# usbasp.net
KiCad netlist of a schematic drawn in EAGLE
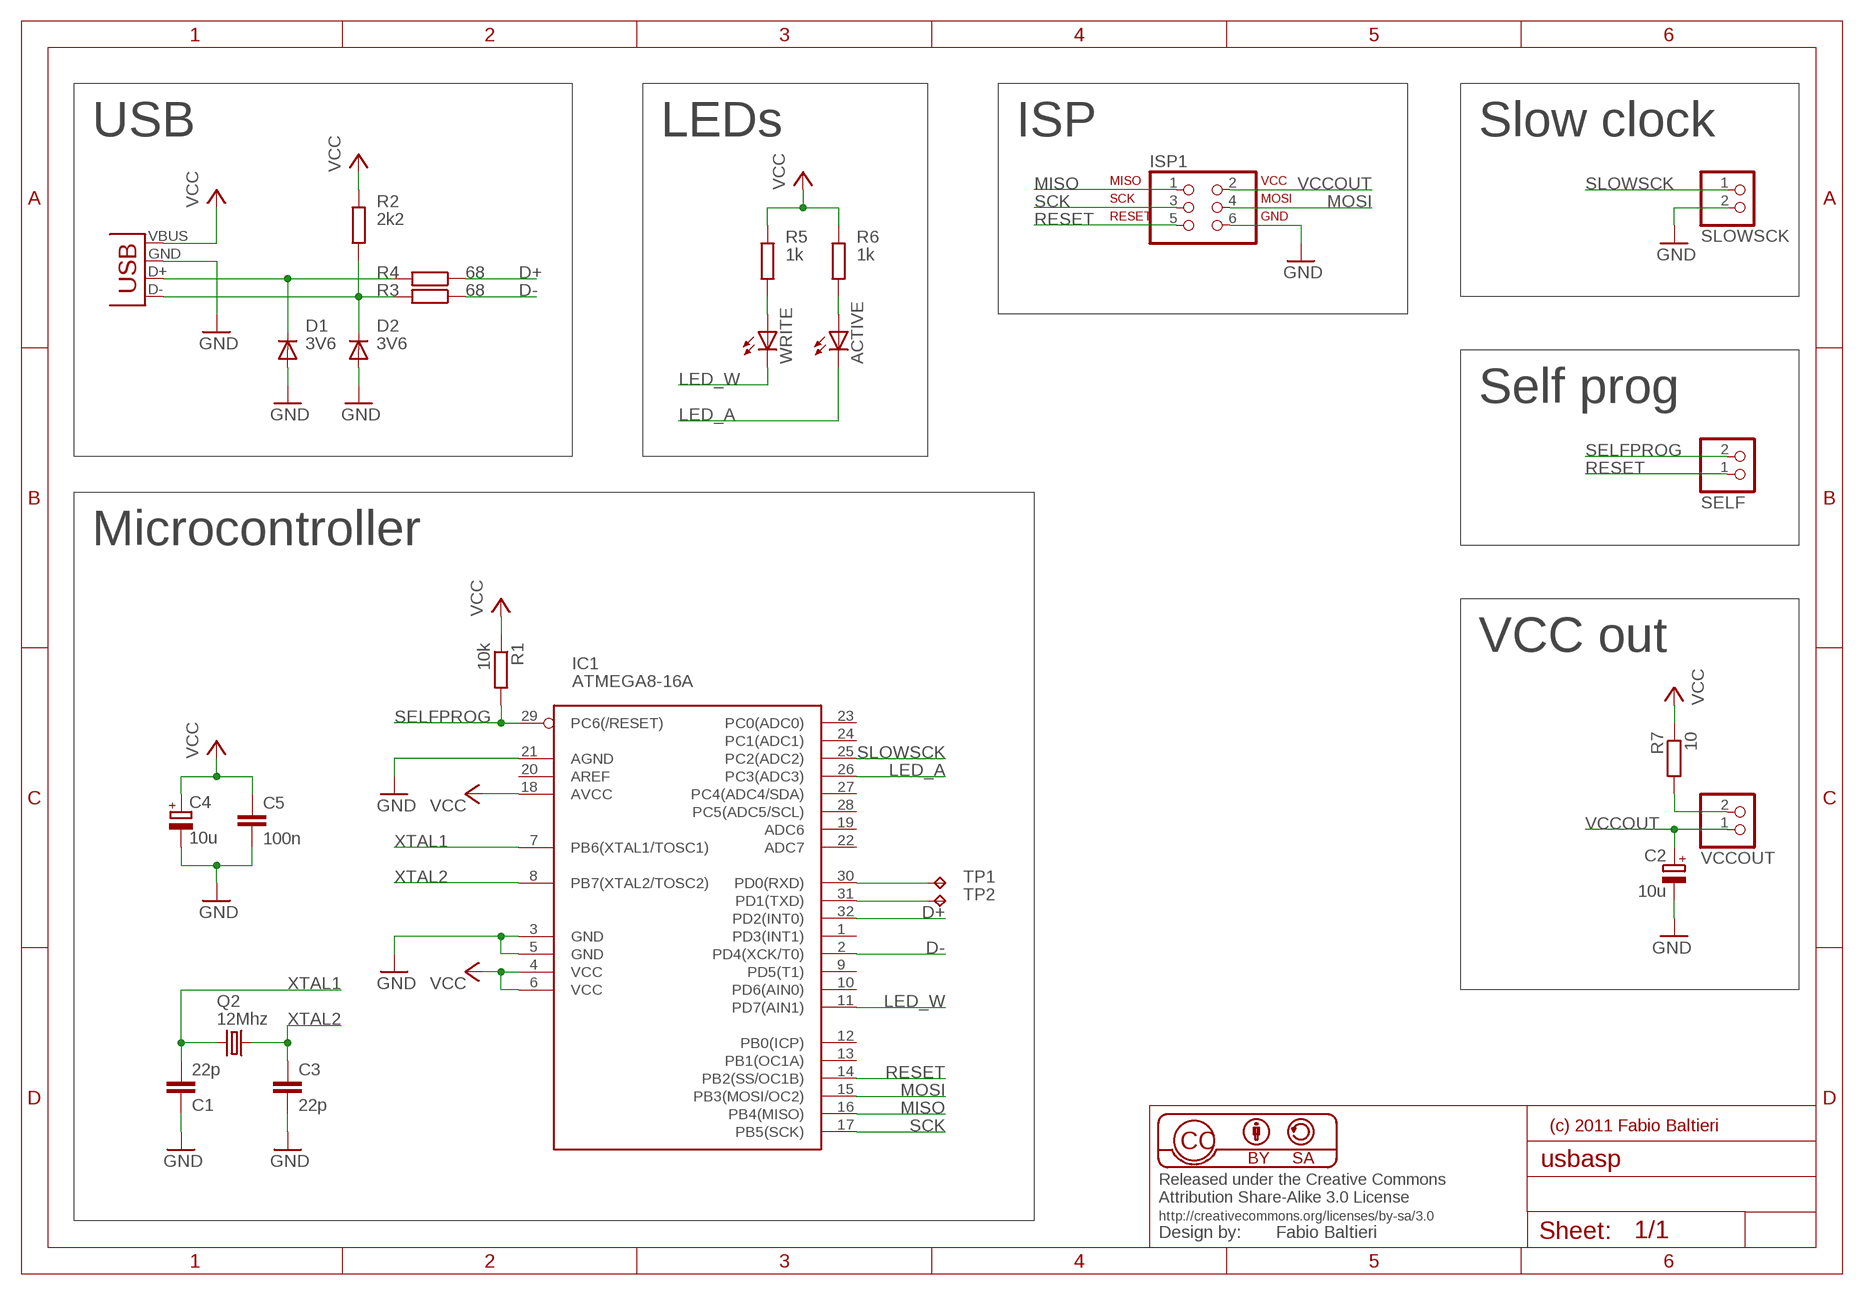
[diagram p0: schematic, sheet 1]

(export (version "E")
  (design (tool "Eeschema 10.0.6"))
  (components
    (comp (ref "ACTIVE")
      (value "LEDCHIP-LED0805")
      (footprint "eagle-import:CHIP-LED0805")
      (libsource (lib "eagle-import") (part "LEDCHIP-LED0805"))
    )
    (comp (ref "C1")
      (value "22p")
      (footprint "eagle-import:C0805")
      (libsource (lib "eagle-import") (part "C-EUC0805"))
    )
    (comp (ref "C2")
      (value "10u")
      (footprint "eagle-import:SMC_A")
      (libsource (lib "eagle-import") (part "CPOL-EUSMCA"))
    )
    (comp (ref "C3")
      (value "22p")
      (footprint "eagle-import:C0805")
      (libsource (lib "eagle-import") (part "C-EUC0805"))
    )
    (comp (ref "C4")
      (value "10u")
      (footprint "eagle-import:SMC_A")
      (libsource (lib "eagle-import") (part "CPOL-EUSMCA"))
    )
    (comp (ref "C5")
      (value "100n")
      (footprint "eagle-import:C0805")
      (libsource (lib "eagle-import") (part "C-EUC0805"))
    )
    (comp (ref "D1")
      (value "3V6")
      (footprint "eagle-import:SMA-DIODE")
      (libsource (lib "eagle-import") (part "DIODESMA"))
    )
    (comp (ref "D2")
      (value "3V6")
      (footprint "eagle-import:SMA-DIODE")
      (libsource (lib "eagle-import") (part "DIODESMA"))
    )
    (comp (ref "IC1")
      (value "ATMEGA8-16A")
      (footprint "eagle-import:TQFP32-08")
      (libsource (lib "eagle-import") (part "ATMEGA8A-16"))
    )
    (comp (ref "ISP1")
      (value "ISP-AVR910SMD")
      (footprint "eagle-import:2X03_BORDER")
      (libsource (lib "eagle-import") (part "ISP-AVR910SMD"))
    )
    (comp (ref "Q2")
      (value "12Mhz")
      (footprint "eagle-import:HC49US")
      (libsource (lib "eagle-import") (part "CRYSTALHC49US"))
    )
    (comp (ref "R1")
      (value "10k")
      (footprint "eagle-import:M0805")
      (libsource (lib "eagle-import") (part "R-EU_M0805"))
    )
    (comp (ref "R2")
      (value "2k2")
      (footprint "eagle-import:M0805")
      (libsource (lib "eagle-import") (part "R-EU_M0805"))
    )
    (comp (ref "R3")
      (value "68")
      (footprint "eagle-import:M0805")
      (libsource (lib "eagle-import") (part "R-EU_M0805"))
    )
    (comp (ref "R4")
      (value "68")
      (footprint "eagle-import:M0805")
      (libsource (lib "eagle-import") (part "R-EU_M0805"))
    )
    (comp (ref "R5")
      (value "1k")
      (footprint "eagle-import:M0805")
      (libsource (lib "eagle-import") (part "R-EU_M0805"))
    )
    (comp (ref "R6")
      (value "1k")
      (footprint "eagle-import:M0805")
      (libsource (lib "eagle-import") (part "R-EU_M0805"))
    )
    (comp (ref "R7")
      (value "10")
      (footprint "eagle-import:M0805")
      (libsource (lib "eagle-import") (part "R-EU_M0805"))
    )
    (comp (ref "SELF")
      (value "PINHD-1X2")
      (footprint "eagle-import:1X02")
      (libsource (lib "eagle-import") (part "PINHD-1X2"))
    )
    (comp (ref "SLOWSCK")
      (value "PINHD-1X2")
      (footprint "eagle-import:1X02")
      (libsource (lib "eagle-import") (part "PINHD-1X2"))
    )
    (comp (ref "TP1")
      (value "TPB1,27")
      (footprint "eagle-import:B1,27")
      (libsource (lib "eagle-import") (part "TPB1,27"))
    )
    (comp (ref "TP2")
      (value "TPB1,27")
      (footprint "eagle-import:B1,27")
      (libsource (lib "eagle-import") (part "TPB1,27"))
    )
    (comp (ref "VCCOUT")
      (value "PINHD-1X2")
      (footprint "eagle-import:1X02")
      (libsource (lib "eagle-import") (part "PINHD-1X2"))
    )
    (comp (ref "WRITE")
      (value "LEDCHIP-LED0805")
      (footprint "eagle-import:CHIP-LED0805")
      (libsource (lib "eagle-import") (part "LEDCHIP-LED0805"))
    )
    (comp (ref "X1")
      (value "USB-A-H")
      (footprint "eagle-import:USB-A-H")
      (libsource (lib "eagle-import") (part "USB-A-H"))
    )
  )
  (nets
    (net (code "1") (name "/D+") (class "Default")
      (node (ref "IC1") (pin "32") (pinfunction "PD2(INT0)_32") (pintype "bidirectional"))
      (node (ref "R4") (pin "1") (pinfunction "1_1") (pintype "passive"))
    )
    (net (code "2") (name "/D-") (class "Default")
      (node (ref "IC1") (pin "2") (pinfunction "PD4(XCK/T0)_2") (pintype "bidirectional"))
      (node (ref "R3") (pin "1") (pinfunction "1_1") (pintype "passive"))
    )
    (net (code "3") (name "/LED_A") (class "Default")
      (node (ref "ACTIVE") (pin "C") (pinfunction "C_C") (pintype "passive"))
      (node (ref "IC1") (pin "26") (pinfunction "PC3(ADC3)_26") (pintype "bidirectional"))
    )
    (net (code "4") (name "/LED_W") (class "Default")
      (node (ref "IC1") (pin "11") (pinfunction "PD7(AIN1)_11") (pintype "bidirectional"))
      (node (ref "WRITE") (pin "C") (pinfunction "C_C") (pintype "passive"))
    )
    (net (code "5") (name "/MISO") (class "Default")
      (node (ref "IC1") (pin "16") (pinfunction "PB4(MISO)_16") (pintype "bidirectional"))
      (node (ref "ISP1") (pin "1") (pinfunction "1_1") (pintype "passive"))
    )
    (net (code "6") (name "/MOSI") (class "Default")
      (node (ref "IC1") (pin "15") (pinfunction "PB3(MOSI/OC2)_15") (pintype "bidirectional"))
      (node (ref "ISP1") (pin "4") (pinfunction "4_4") (pintype "passive"))
    )
    (net (code "7") (name "/RESET") (class "Default")
      (node (ref "IC1") (pin "14") (pinfunction "PB2(SS/OC1B)_14") (pintype "bidirectional"))
      (node (ref "ISP1") (pin "5") (pinfunction "5_5") (pintype "passive"))
      (node (ref "SELF") (pin "1") (pinfunction "1_1") (pintype "passive"))
    )
    (net (code "8") (name "/SCK") (class "Default")
      (node (ref "IC1") (pin "17") (pinfunction "PB5(SCK)_17") (pintype "bidirectional"))
      (node (ref "ISP1") (pin "3") (pinfunction "3_3") (pintype "passive"))
    )
    (net (code "9") (name "/SELFPROG") (class "Default")
      (node (ref "IC1") (pin "29") (pinfunction "PC6(/RESET)_29") (pintype "bidirectional"))
      (node (ref "R1") (pin "2") (pinfunction "2_2") (pintype "passive"))
      (node (ref "SELF") (pin "2") (pinfunction "2_2") (pintype "passive"))
    )
    (net (code "10") (name "/SLOWSCK") (class "Default")
      (node (ref "IC1") (pin "25") (pinfunction "PC2(ADC2)_25") (pintype "bidirectional"))
      (node (ref "SLOWSCK") (pin "1") (pinfunction "1_1") (pintype "passive"))
    )
    (net (code "11") (name "/VCCOUT") (class "Default")
      (node (ref "C2") (pin "+") (pinfunction "+_+") (pintype "passive"))
      (node (ref "ISP1") (pin "2") (pinfunction "2_2") (pintype "passive"))
      (node (ref "VCCOUT") (pin "1") (pinfunction "1_1") (pintype "passive"))
    )
    (net (code "12") (name "/XTAL1") (class "Default")
      (node (ref "C1") (pin "2") (pinfunction "2_2") (pintype "passive"))
      (node (ref "IC1") (pin "7") (pinfunction "PB6(XTAL1/TOSC1)_7") (pintype "bidirectional"))
      (node (ref "Q2") (pin "2") (pinfunction "2_2") (pintype "passive"))
    )
    (net (code "13") (name "/XTAL2") (class "Default")
      (node (ref "C3") (pin "2") (pinfunction "2_2") (pintype "passive"))
      (node (ref "IC1") (pin "8") (pinfunction "PB7(XTAL2/TOSC2)_8") (pintype "bidirectional"))
      (node (ref "Q2") (pin "1") (pinfunction "1_1") (pintype "passive"))
    )
    (net (code "14") (name "GND") (class "Default")
      (node (ref "C1") (pin "1") (pinfunction "1_1") (pintype "passive"))
      (node (ref "C2") (pin "-") (pinfunction "-_-") (pintype "passive"))
      (node (ref "C3") (pin "1") (pinfunction "1_1") (pintype "passive"))
      (node (ref "C4") (pin "-") (pinfunction "-_-") (pintype "passive"))
      (node (ref "C5") (pin "2") (pinfunction "2_2") (pintype "passive"))
      (node (ref "D1") (pin "A") (pinfunction "A_A") (pintype "passive"))
      (node (ref "D2") (pin "A") (pinfunction "A_A") (pintype "passive"))
      (node (ref "IC1") (pin "21") (pinfunction "AGND_21") (pintype "bidirectional"))
      (node (ref "IC1") (pin "3") (pinfunction "GND_3") (pintype "bidirectional"))
      (node (ref "IC1") (pin "5") (pinfunction "GND_5") (pintype "bidirectional"))
      (node (ref "ISP1") (pin "6") (pinfunction "6_6") (pintype "passive"))
      (node (ref "SLOWSCK") (pin "2") (pinfunction "2_2") (pintype "passive"))
      (node (ref "X1") (pin "GND") (pinfunction "VBUS_GND") (pintype "bidirectional"))
    )
    (net (code "15") (name "Net-(ACTIVE-PadA)") (class "Default")
      (node (ref "ACTIVE") (pin "A") (pinfunction "A_A") (pintype "passive"))
      (node (ref "R6") (pin "2") (pinfunction "2_2") (pintype "passive"))
    )
    (net (code "16") (name "Net-(IC1-PD0(RXD))") (class "Default")
      (node (ref "IC1") (pin "30") (pinfunction "PD0(RXD)_30") (pintype "bidirectional"))
      (node (ref "TP1") (pin "TP") (pinfunction "TP_TP") (pintype "input"))
    )
    (net (code "17") (name "Net-(IC1-PD1(TXD))") (class "Default")
      (node (ref "IC1") (pin "31") (pinfunction "PD1(TXD)_31") (pintype "bidirectional"))
      (node (ref "TP2") (pin "TP") (pinfunction "TP_TP") (pintype "input"))
    )
    (net (code "18") (name "Net-(R5-Pad2)") (class "Default")
      (node (ref "R5") (pin "2") (pinfunction "2_2") (pintype "passive"))
      (node (ref "WRITE") (pin "A") (pinfunction "A_A") (pintype "passive"))
    )
    (net (code "19") (name "Net-(R7-Pad2)") (class "Default")
      (node (ref "R7") (pin "2") (pinfunction "2_2") (pintype "passive"))
      (node (ref "VCCOUT") (pin "2") (pinfunction "2_2") (pintype "passive"))
    )
    (net (code "20") (name "Net-(X1-D+)") (class "Default")
      (node (ref "D2") (pin "C") (pinfunction "C_C") (pintype "passive"))
      (node (ref "R2") (pin "1") (pinfunction "1_1") (pintype "passive"))
      (node (ref "R3") (pin "2") (pinfunction "2_2") (pintype "passive"))
      (node (ref "X1") (pin "D-") (pinfunction "D+_D-") (pintype "bidirectional"))
    )
    (net (code "21") (name "Net-(X1-D-)") (class "Default")
      (node (ref "D1") (pin "C") (pinfunction "C_C") (pintype "passive"))
      (node (ref "R4") (pin "2") (pinfunction "2_2") (pintype "passive"))
      (node (ref "X1") (pin "D+") (pinfunction "D-_D+") (pintype "bidirectional"))
    )
    (net (code "22") (name "VCC") (class "Default")
      (node (ref "C4") (pin "+") (pinfunction "+_+") (pintype "passive"))
      (node (ref "C5") (pin "1") (pinfunction "1_1") (pintype "passive"))
      (node (ref "IC1") (pin "18") (pinfunction "AVCC_18") (pintype "bidirectional"))
      (node (ref "IC1") (pin "4") (pinfunction "VCC_4") (pintype "bidirectional"))
      (node (ref "IC1") (pin "6") (pinfunction "VCC_6") (pintype "bidirectional"))
      (node (ref "R1") (pin "1") (pinfunction "1_1") (pintype "passive"))
      (node (ref "R2") (pin "2") (pinfunction "2_2") (pintype "passive"))
      (node (ref "R5") (pin "1") (pinfunction "1_1") (pintype "passive"))
      (node (ref "R6") (pin "1") (pinfunction "1_1") (pintype "passive"))
      (node (ref "R7") (pin "1") (pinfunction "1_1") (pintype "passive"))
      (node (ref "X1") (pin "VBUS") (pinfunction "GND_VBUS") (pintype "bidirectional"))
    )
    (net (code "23") (name "unconnected-(IC1-ADC6-Pad19)") (class "Default")
      (node (ref "IC1") (pin "19") (pinfunction "ADC6_19") (pintype "bidirectional"))
    )
    (net (code "24") (name "unconnected-(IC1-ADC7-Pad22)") (class "Default")
      (node (ref "IC1") (pin "22") (pinfunction "ADC7_22") (pintype "bidirectional"))
    )
    (net (code "25") (name "unconnected-(IC1-AREF-Pad20)") (class "Default")
      (node (ref "IC1") (pin "20") (pinfunction "AREF_20") (pintype "bidirectional"))
    )
    (net (code "26") (name "unconnected-(IC1-PB0(ICP)-Pad12)") (class "Default")
      (node (ref "IC1") (pin "12") (pinfunction "PB0(ICP)_12") (pintype "bidirectional"))
    )
    (net (code "27") (name "unconnected-(IC1-PB1(OC1A)-Pad13)") (class "Default")
      (node (ref "IC1") (pin "13") (pinfunction "PB1(OC1A)_13") (pintype "bidirectional"))
    )
    (net (code "28") (name "unconnected-(IC1-PC0(ADC0)-Pad23)") (class "Default")
      (node (ref "IC1") (pin "23") (pinfunction "PC0(ADC0)_23") (pintype "bidirectional"))
    )
    (net (code "29") (name "unconnected-(IC1-PC1(ADC1)-Pad24)") (class "Default")
      (node (ref "IC1") (pin "24") (pinfunction "PC1(ADC1)_24") (pintype "bidirectional"))
    )
    (net (code "30") (name "unconnected-(IC1-PC4(ADC4{slash}SDA)-Pad27)") (class "Default")
      (node (ref "IC1") (pin "27") (pinfunction "PC4(ADC4/SDA)_27") (pintype "bidirectional"))
    )
    (net (code "31") (name "unconnected-(IC1-PC5(ADC5{slash}SCL)-Pad28)") (class "Default")
      (node (ref "IC1") (pin "28") (pinfunction "PC5(ADC5/SCL)_28") (pintype "bidirectional"))
    )
    (net (code "32") (name "unconnected-(IC1-PD3(INT1)-Pad1)") (class "Default")
      (node (ref "IC1") (pin "1") (pinfunction "PD3(INT1)_1") (pintype "bidirectional"))
    )
    (net (code "33") (name "unconnected-(IC1-PD5(T1)-Pad9)") (class "Default")
      (node (ref "IC1") (pin "9") (pinfunction "PD5(T1)_9") (pintype "bidirectional"))
    )
    (net (code "34") (name "unconnected-(IC1-PD6(AIN0)-Pad10)") (class "Default")
      (node (ref "IC1") (pin "10") (pinfunction "PD6(AIN0)_10") (pintype "bidirectional"))
    )
  )
)
